# GRLV_DoubleRail_V0_1.net
KiCad netlist of a schematic drawn in Altium Designer
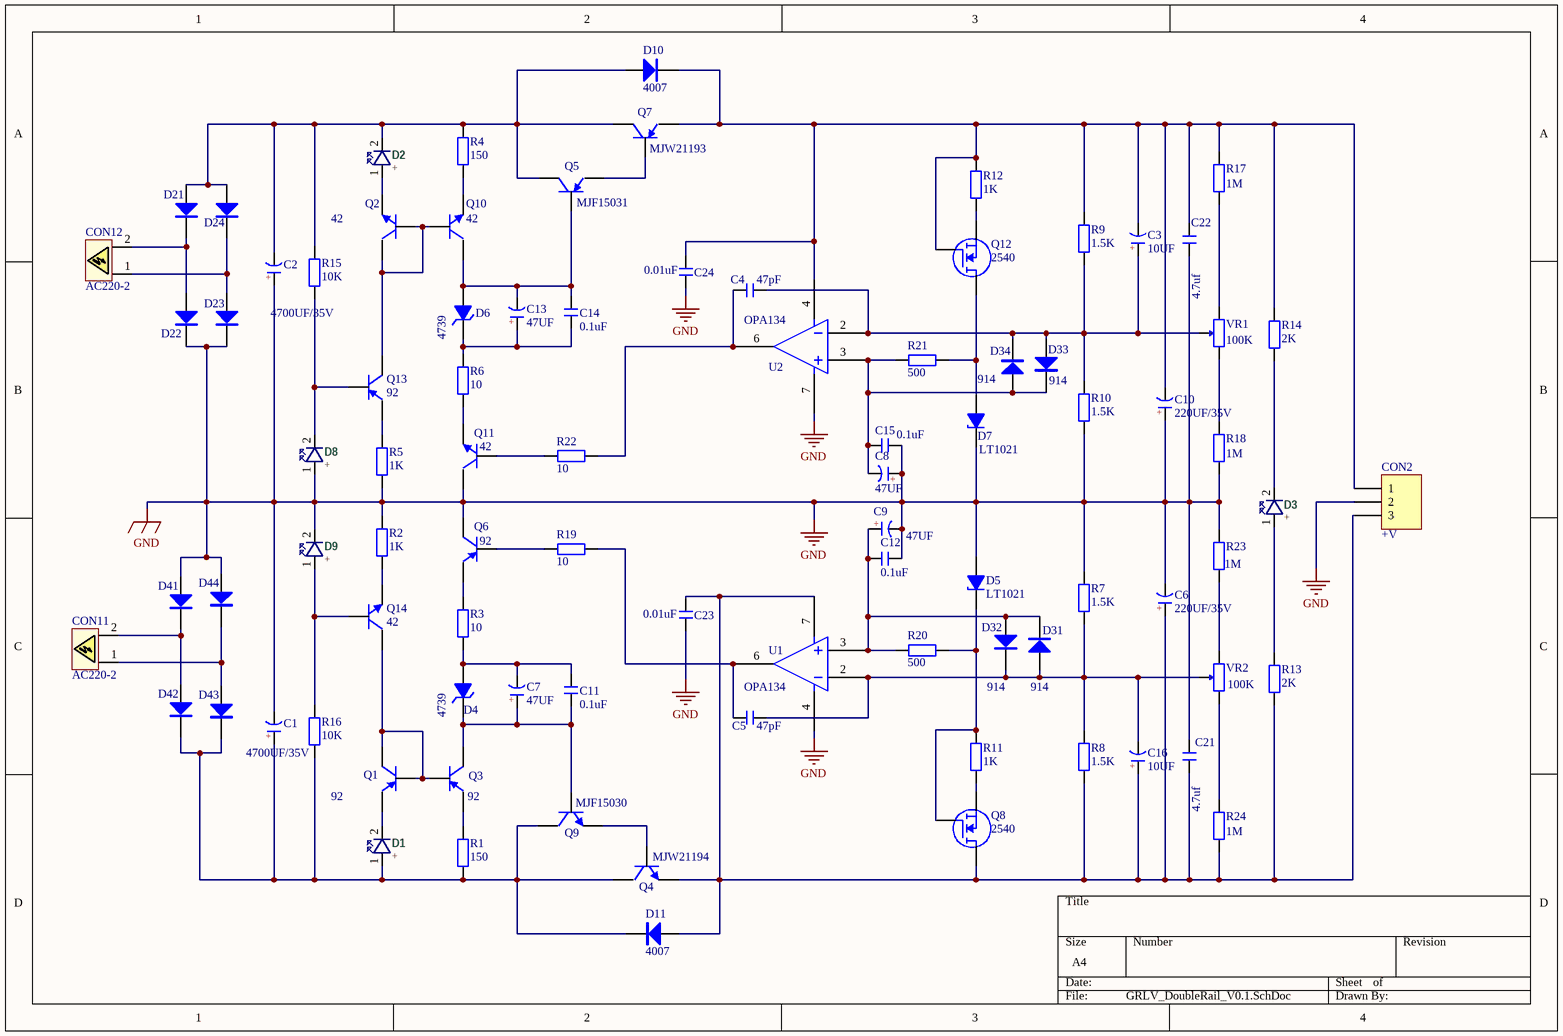
[diagram p0: GRLV_DoubleRail_V0.1.SchDoc]

(export (version "E")
  (design (tool "Eeschema 10.0.6"))
  (components
    (comp (ref "C1")
      (value "4700UF/35V")
      (footprint "CAP 11*35*60")
      (description "直插电解电容")
      (fields (field (name "版权归属") "源创客"))
      (libsource (lib "电阻-电容-电感") (part "C-CAP"))
    )
    (comp (ref "C2")
      (value "4700UF/35V")
      (footprint "CAP 11*35*60")
      (description "直插电解电容")
      (fields (field (name "版权归属") "源创客"))
      (libsource (lib "电阻-电容-电感") (part "C-CAP"))
    )
    (comp (ref "C3")
      (value "10UF")
      (footprint "CAP 2.5*6.3*7")
      (description "直插电解电容")
      (fields (field (name "版权归属") "源创客"))
      (libsource (lib "电阻-电容-电感") (part "C-CAP"))
    )
    (comp (ref "C4")
      (value "47pF")
      (footprint "CBB 6.3*6.3*5")
      (description "CBB电容")
      (fields (field (name "版权归属") "源创客"))
      (libsource (lib "电阻-电容-电感") (part "C-CBB"))
    )
    (comp (ref "C5")
      (value "47pF")
      (footprint "CBB 6.3*6.3*5")
      (description "CBB电容")
      (fields (field (name "版权归属") "源创客"))
      (libsource (lib "电阻-电容-电感") (part "C-CBB"))
    )
    (comp (ref "C6")
      (value "220UF/35V")
      (footprint "CAP 3.5*8*11.5")
      (description "直插电解电容")
      (fields (field (name "版权归属") "源创客"))
      (libsource (lib "电阻-电容-电感") (part "C-CAP"))
    )
    (comp (ref "C7")
      (value "47UF")
      (footprint "CAP 2.5*6.3*11.2")
      (description "直插电解电容")
      (fields (field (name "版权归属") "源创客"))
      (libsource (lib "电阻-电容-电感") (part "C-CAP"))
    )
    (comp (ref "C8")
      (value "47UF")
      (footprint "CAP 2.5*6.3*11.2")
      (description "直插电解电容")
      (fields (field (name "版权归属") "源创客"))
      (libsource (lib "") (part "C-CAP_1"))
    )
    (comp (ref "C9")
      (value "47UF")
      (footprint "CAP 2.5*6.3*11.2")
      (description "直插电解电容")
      (fields (field (name "版权归属") "源创客"))
      (libsource (lib "") (part "C-CAP_1"))
    )
    (comp (ref "C10")
      (value "220UF/35V")
      (footprint "CAP 3.5*8*11.5")
      (description "直插电解电容")
      (fields (field (name "版权归属") "源创客"))
      (libsource (lib "电阻-电容-电感") (part "C-CAP"))
    )
    (comp (ref "C11")
      (value "0.1uF")
      (footprint "CBB 6.3*6.3*5")
      (description "CBB电容")
      (fields (field (name "版权归属") "源创客"))
      (libsource (lib "电阻-电容-电感") (part "C-CBB"))
    )
    (comp (ref "C12")
      (value "0.1uF")
      (footprint "CBB 6.3*6.3*5")
      (description "CBB电容")
      (fields (field (name "版权归属") "源创客"))
      (libsource (lib "电阻-电容-电感") (part "C-CBB"))
    )
    (comp (ref "C13")
      (value "47UF")
      (footprint "CAP 2.5*6.3*11.2")
      (description "直插电解电容")
      (fields (field (name "版权归属") "源创客"))
      (libsource (lib "电阻-电容-电感") (part "C-CAP"))
    )
    (comp (ref "C14")
      (value "0.1uF")
      (footprint "CBB 6.3*6.3*5")
      (description "CBB电容")
      (fields (field (name "版权归属") "源创客"))
      (libsource (lib "电阻-电容-电感") (part "C-CBB"))
    )
    (comp (ref "C15")
      (value "0.1uF")
      (footprint "CBB 6.3*6.3*5")
      (description "CBB电容")
      (fields (field (name "版权归属") "源创客"))
      (libsource (lib "电阻-电容-电感") (part "C-CBB"))
    )
    (comp (ref "C16")
      (value "10UF")
      (footprint "CAP 2.5*6.3*7")
      (description "直插电解电容")
      (fields (field (name "版权归属") "源创客"))
      (libsource (lib "电阻-电容-电感") (part "C-CAP"))
    )
    (comp (ref "C21")
      (value "4.7uf")
      (footprint "CBB 7.2*7.2*13")
      (description "MKS薄膜电容")
      (libsource (lib "电阻-电容-电感") (part "C-MKS"))
    )
    (comp (ref "C22")
      (value "4.7uf")
      (footprint "CBB 7.2*7.2*13")
      (description "MKS薄膜电容")
      (libsource (lib "电阻-电容-电感") (part "C-MKS"))
    )
    (comp (ref "C23")
      (value "0.01uF")
      (footprint "CBB 6.3*6.3*5")
      (description "CBB电容")
      (fields (field (name "Comment") ".01") (field (name "版权归属") "源创客"))
      (libsource (lib "电阻-电容-电感") (part "C-CBB"))
    )
    (comp (ref "C24")
      (value "0.01uF")
      (footprint "CBB 6.3*6.3*5")
      (description "CBB电容")
      (fields (field (name "Comment") ".01") (field (name "版权归属") "源创客"))
      (libsource (lib "电阻-电容-电感") (part "C-CBB"))
    )
    (comp (ref "CON2")
      (value "+V")
      (footprint "HX5.08-3S")
      (libsource (lib "Connectors") (part "EDG5.08-3P"))
    )
    (comp (ref "CON11")
      (value "AC220-2")
      (footprint "HX5.08-2S")
      (libsource (lib "Connectors") (part "AC220-2"))
    )
    (comp (ref "CON12")
      (value "AC220-2")
      (footprint "HX5.08-2S")
      (libsource (lib "Connectors") (part "AC220-2"))
    )
    (comp (ref "D1")
      (value "+")
      (footprint "LED 3MM-R")
      (description "直插式LED")
      (libsource (lib "LED") (part "LED"))
    )
    (comp (ref "D2")
      (value "+")
      (footprint "LED 3MM-R")
      (description "直插式LED")
      (libsource (lib "LED") (part "LED"))
    )
    (comp (ref "D3")
      (value "+")
      (footprint "LED 3MM-R")
      (description "直插式LED")
      (libsource (lib "LED") (part "LED"))
    )
    (comp (ref "D4")
      (value "4739")
      (footprint "DO-41")
      (description "9.1V/1W稳压管")
      (libsource (lib "二极管-整流桥") (part "1N4739"))
    )
    (comp (ref "D5")
      (value "LT1021")
      (footprint "DIP8-300_MH")
      (description "10V Precision Reference 2 Pin Config")
      (libsource (lib "电压参考") (part "LT1021-10-2P"))
    )
    (comp (ref "D6")
      (value "4739")
      (footprint "DO-41")
      (description "9.1V/1W稳压管")
      (libsource (lib "二极管-整流桥") (part "1N4739"))
    )
    (comp (ref "D7")
      (value "LT1021")
      (footprint "DIP8-300_MH")
      (description "10V Precision Reference 2 Pin Config")
      (libsource (lib "电压参考") (part "LT1021-10-2P"))
    )
    (comp (ref "D8")
      (value "+")
      (footprint "LED 3MM-R")
      (description "直插式LED")
      (libsource (lib "LED") (part "LED"))
    )
    (comp (ref "D9")
      (value "+")
      (footprint "LED 3MM-R")
      (description "直插式LED")
      (libsource (lib "LED") (part "LED"))
    )
    (comp (ref "D10")
      (value "4007")
      (footprint "DO-41")
      (description "整流二极管")
      (fields (field (name "版权归属") "源创客"))
      (libsource (lib "二极管-整流桥") (part "1N4007"))
    )
    (comp (ref "D11")
      (value "4007")
      (footprint "DO-41")
      (description "整流二极管")
      (fields (field (name "版权归属") "源创客"))
      (libsource (lib "二极管-整流桥") (part "1N4007"))
    )
    (comp (ref "D21")
      (value "HFA08")
      (footprint "TO220AC")
      (description "Ultrafast Soft Recovery Diado 8A 600V")
      (libsource (lib "二极管-整流桥") (part "VS-HFA08TB60-M3"))
    )
    (comp (ref "D22")
      (value "HFA08")
      (footprint "TO220AC")
      (description "Ultrafast Soft Recovery Diado 8A 600V")
      (libsource (lib "二极管-整流桥") (part "VS-HFA08TB60-M3"))
    )
    (comp (ref "D23")
      (value "HFA08")
      (footprint "TO220AC")
      (description "Ultrafast Soft Recovery Diado 8A 600V")
      (libsource (lib "二极管-整流桥") (part "VS-HFA08TB60-M3"))
    )
    (comp (ref "D24")
      (value "HFA08")
      (footprint "TO220AC")
      (description "Ultrafast Soft Recovery Diado 8A 600V")
      (libsource (lib "二极管-整流桥") (part "VS-HFA08TB60-M3"))
    )
    (comp (ref "D31")
      (value "914")
      (footprint "DO-35")
      (description "高速开关管 1V/0.25W")
      (libsource (lib "二极管-整流桥") (part "1N914"))
    )
    (comp (ref "D32")
      (value "914")
      (footprint "DO-35")
      (description "高速开关管 1V/0.25W")
      (libsource (lib "二极管-整流桥") (part "1N914"))
    )
    (comp (ref "D33")
      (value "914")
      (footprint "DO-35")
      (description "高速开关管 1V/0.25W")
      (libsource (lib "二极管-整流桥") (part "1N914"))
    )
    (comp (ref "D34")
      (value "914")
      (footprint "DO-35")
      (description "高速开关管 1V/0.25W")
      (libsource (lib "二极管-整流桥") (part "1N914"))
    )
    (comp (ref "D41")
      (value "VS-HFA08TB60-M3")
      (footprint "TO220AC")
      (description "Ultrafast Soft Recovery Diado 8A 600V")
      (libsource (lib "二极管-整流桥") (part "VS-HFA08TB60-M3"))
    )
    (comp (ref "D42")
      (value "VS-HFA08TB60-M3")
      (footprint "TO220AC")
      (description "Ultrafast Soft Recovery Diado 8A 600V")
      (libsource (lib "二极管-整流桥") (part "VS-HFA08TB60-M3"))
    )
    (comp (ref "D43")
      (value "VS-HFA08TB60-M3")
      (footprint "TO220AC")
      (description "Ultrafast Soft Recovery Diado 8A 600V")
      (libsource (lib "二极管-整流桥") (part "VS-HFA08TB60-M3"))
    )
    (comp (ref "D44")
      (value "VS-HFA08TB60-M3")
      (footprint "TO220AC")
      (description "Ultrafast Soft Recovery Diado 8A 600V")
      (libsource (lib "二极管-整流桥") (part "VS-HFA08TB60-M3"))
    )
    (comp (ref "Q1")
      (value "92")
      (footprint "TO92A")
      (description "High Voltage PNP Transistor")
      (libsource (lib "三极管") (part "KSP92/93"))
    )
    (comp (ref "Q2")
      (value "42")
      (footprint "TO92A")
      (description "High Voltage NPN Transistor")
      (libsource (lib "三极管") (part "KSP42/43"))
    )
    (comp (ref "Q3")
      (value "92")
      (footprint "TO92A")
      (description "High Voltage PNP Transistor")
      (libsource (lib "三极管") (part "KSP92/93"))
    )
    (comp (ref "Q4")
      (value "MJW21194")
      (footprint "TO247V")
      (description "Power NPN Transistor")
      (libsource (lib "三极管") (part "MJW21194"))
    )
    (comp (ref "Q5")
      (value "MJF15031")
      (footprint "TO220V")
      (description "Power PNP Transistor")
      (libsource (lib "三极管") (part "MJF15031"))
    )
    (comp (ref "Q6")
      (value "92")
      (footprint "TO92A")
      (description "High Voltage PNP Transistor")
      (libsource (lib "三极管") (part "KSP92/93"))
    )
    (comp (ref "Q7")
      (value "MJW21193")
      (footprint "TO247V")
      (description "Power PNP Transistor")
      (libsource (lib "三极管") (part "MJW21193"))
    )
    (comp (ref "Q8")
      (value "2540")
      (footprint "TO92A")
      (description "N沟道耗尽型DMOS场效应管 400V/150ma")
      (libsource (lib "场效应管") (part "DN2540"))
    )
    (comp (ref "Q9")
      (value "MJF15030")
      (footprint "TO220V")
      (description "Power NPN Transistor")
      (libsource (lib "三极管") (part "MJF15030"))
    )
    (comp (ref "Q10")
      (value "42")
      (footprint "TO92A")
      (description "High Voltage NPN Transistor")
      (libsource (lib "三极管") (part "KSP42/43"))
    )
    (comp (ref "Q11")
      (value "42")
      (footprint "TO92A")
      (description "High Voltage NPN Transistor")
      (libsource (lib "三极管") (part "KSP42/43"))
    )
    (comp (ref "Q12")
      (value "2540")
      (footprint "TO92A")
      (description "N沟道耗尽型DMOS场效应管 400V/150ma")
      (libsource (lib "场效应管") (part "DN2540"))
    )
    (comp (ref "Q13")
      (value "92")
      (footprint "TO92A")
      (description "High Voltage PNP Transistor")
      (libsource (lib "三极管") (part "KSP92/93"))
    )
    (comp (ref "Q14")
      (value "42")
      (footprint "TO92A")
      (description "High Voltage NPN Transistor")
      (libsource (lib "三极管") (part "KSP42/43"))
    )
    (comp (ref "R1")
      (value "150")
      (footprint "RS 1/4W")
      (description "直插色环电阻")
      (fields (field (name "版权归属") "源创客"))
      (libsource (lib "电阻-电容-电感") (part "R-CRR"))
    )
    (comp (ref "R2")
      (value "1K")
      (footprint "RS 1/4W")
      (description "直插色环电阻")
      (fields (field (name "版权归属") "源创客"))
      (libsource (lib "电阻-电容-电感") (part "R-CRR"))
    )
    (comp (ref "R3")
      (value "10")
      (footprint "RS 1/4W")
      (description "直插色环电阻")
      (fields (field (name "版权归属") "源创客"))
      (libsource (lib "电阻-电容-电感") (part "R-CRR"))
    )
    (comp (ref "R4")
      (value "150")
      (footprint "RS 1/4W")
      (description "直插色环电阻")
      (fields (field (name "版权归属") "源创客"))
      (libsource (lib "电阻-电容-电感") (part "R-CRR"))
    )
    (comp (ref "R5")
      (value "1K")
      (footprint "RS 1/4W")
      (description "直插色环电阻")
      (fields (field (name "版权归属") "源创客"))
      (libsource (lib "电阻-电容-电感") (part "R-CRR"))
    )
    (comp (ref "R6")
      (value "10")
      (footprint "RS 1/4W")
      (description "直插色环电阻")
      (fields (field (name "版权归属") "源创客"))
      (libsource (lib "电阻-电容-电感") (part "R-CRR"))
    )
    (comp (ref "R7")
      (value "1.5K")
      (footprint "RS 1/4W")
      (description "直插色环电阻")
      (fields (field (name "版权归属") "源创客"))
      (libsource (lib "电阻-电容-电感") (part "R-CRR"))
    )
    (comp (ref "R8")
      (value "1.5K")
      (footprint "RS 1/4W")
      (description "直插色环电阻")
      (fields (field (name "版权归属") "源创客"))
      (libsource (lib "电阻-电容-电感") (part "R-CRR"))
    )
    (comp (ref "R9")
      (value "1.5K")
      (footprint "RS 1/4W")
      (description "直插色环电阻")
      (fields (field (name "版权归属") "源创客"))
      (libsource (lib "电阻-电容-电感") (part "R-CRR"))
    )
    (comp (ref "R10")
      (value "1.5K")
      (footprint "RS 1/4W")
      (description "直插色环电阻")
      (fields (field (name "版权归属") "源创客"))
      (libsource (lib "电阻-电容-电感") (part "R-CRR"))
    )
    (comp (ref "R11")
      (value "1K")
      (footprint "RS 1/4W")
      (description "直插色环电阻")
      (fields (field (name "版权归属") "源创客"))
      (libsource (lib "电阻-电容-电感") (part "R-CRR"))
    )
    (comp (ref "R12")
      (value "1K")
      (footprint "RS 1/4W")
      (description "直插色环电阻")
      (fields (field (name "版权归属") "源创客"))
      (libsource (lib "电阻-电容-电感") (part "R-CRR"))
    )
    (comp (ref "R13")
      (value "2K")
      (footprint "RS 1/4W")
      (description "直插色环电阻")
      (fields (field (name "版权归属") "源创客"))
      (libsource (lib "电阻-电容-电感") (part "R-CRR"))
    )
    (comp (ref "R14")
      (value "2K")
      (footprint "RS 1/4W")
      (description "直插色环电阻")
      (fields (field (name "版权归属") "源创客"))
      (libsource (lib "电阻-电容-电感") (part "R-CRR"))
    )
    (comp (ref "R15")
      (value "10K")
      (footprint "RS 1/4W")
      (description "直插色环电阻")
      (fields (field (name "版权归属") "源创客"))
      (libsource (lib "电阻-电容-电感") (part "R-CRR"))
    )
    (comp (ref "R16")
      (value "10K")
      (footprint "RS 1/4W")
      (description "直插色环电阻")
      (fields (field (name "版权归属") "源创客"))
      (libsource (lib "电阻-电容-电感") (part "R-CRR"))
    )
    (comp (ref "R17")
      (value "1M")
      (footprint "RS 1/4W")
      (description "直插色环电阻")
      (fields (field (name "版权归属") "源创客"))
      (libsource (lib "电阻-电容-电感") (part "R-CRR"))
    )
    (comp (ref "R18")
      (value "1M")
      (footprint "RS 1/4W")
      (description "直插色环电阻")
      (fields (field (name "版权归属") "源创客"))
      (libsource (lib "电阻-电容-电感") (part "R-CRR"))
    )
    (comp (ref "R19")
      (value "10")
      (footprint "RS 1/4W")
      (description "直插色环电阻")
      (fields (field (name "版权归属") "源创客"))
      (libsource (lib "电阻-电容-电感") (part "R-CRR"))
    )
    (comp (ref "R20")
      (value "500")
      (footprint "RS 1/4W")
      (description "直插色环电阻")
      (fields (field (name "版权归属") "源创客"))
      (libsource (lib "电阻-电容-电感") (part "R-CRR"))
    )
    (comp (ref "R21")
      (value "500")
      (footprint "RS 1/4W")
      (description "直插色环电阻")
      (fields (field (name "版权归属") "源创客"))
      (libsource (lib "电阻-电容-电感") (part "R-CRR"))
    )
    (comp (ref "R22")
      (value "10")
      (footprint "RS 1/4W")
      (description "直插色环电阻")
      (fields (field (name "版权归属") "源创客"))
      (libsource (lib "电阻-电容-电感") (part "R-CRR"))
    )
    (comp (ref "R23")
      (value "1M")
      (footprint "RS 1/4W")
      (description "直插色环电阻")
      (fields (field (name "版权归属") "源创客"))
      (libsource (lib "电阻-电容-电感") (part "R-CRR"))
    )
    (comp (ref "R24")
      (value "1M")
      (footprint "RS 1/4W")
      (description "直插色环电阻")
      (fields (field (name "版权归属") "源创客"))
      (libsource (lib "电阻-电容-电感") (part "R-CRR"))
    )
    (comp (ref "U1") (value "OPA134") (footprint "DIP8-300_MH") (libsource (lib "运放") (part "OPA134PA")))
    (comp (ref "U2") (value "OPA134") (footprint "DIP8-300_MH") (libsource (lib "运放") (part "OPA134PA")))
    (comp (ref "VR1")
      (value "100K")
      (footprint "RS 1/2W-VR")
      (description "直插可调电阻-顶调")
      (libsource (lib "电阻-电容-电感") (part "VR-W"))
    )
    (comp (ref "VR2")
      (value "100K")
      (footprint "RS 1/2W-VR")
      (description "直插可调电阻-顶调")
      (libsource (lib "电阻-电容-电感") (part "VR-W"))
    )
  )
  (nets
    (net (code "1") (name "GND") (class "Default")
      (node (ref "C1") (pin "2") (pinfunction "K_2") (pintype "passive"))
      (node (ref "C10") (pin "1") (pinfunction "A_1") (pintype "passive"))
      (node (ref "C12") (pin "2") (pinfunction "2_2") (pintype "passive"))
      (node (ref "C15") (pin "2") (pinfunction "2_2") (pintype "passive"))
      (node (ref "C2") (pin "1") (pinfunction "A_1") (pintype "passive"))
      (node (ref "C21") (pin "2") (pinfunction "2_2") (pintype "passive"))
      (node (ref "C22") (pin "1") (pinfunction "1_1") (pintype "passive"))
      (node (ref "C23") (pin "1") (pinfunction "1_1") (pintype "passive"))
      (node (ref "C24") (pin "1") (pinfunction "1_1") (pintype "passive"))
      (node (ref "C6") (pin "2") (pinfunction "K_2") (pintype "passive"))
      (node (ref "C8") (pin "1") (pinfunction "A_1") (pintype "passive"))
      (node (ref "C9") (pin "2") (pinfunction "K_2") (pintype "passive"))
      (node (ref "CON2") (pin "2") (pinfunction "2_2") (pintype "passive"))
      (node (ref "D22") (pin "1") (pinfunction "Cathode_1") (pintype "passive"))
      (node (ref "D23") (pin "1") (pinfunction "Cathode_1") (pintype "passive"))
      (node (ref "D41") (pin "2") (pinfunction "Anode_2") (pintype "passive"))
      (node (ref "D44") (pin "2") (pinfunction "Anode_2") (pintype "passive"))
      (node (ref "D5") (pin "4") (pinfunction "A_4") (pintype "passive"))
      (node (ref "D7") (pin "6") (pinfunction "K_6") (pintype "passive"))
      (node (ref "D8") (pin "1") (pinfunction "A_1") (pintype "passive"))
      (node (ref "D9") (pin "2") (pinfunction "K_2") (pintype "passive"))
      (node (ref "Q11") (pin "3") (pinfunction "C_3") (pintype "passive"))
      (node (ref "Q6") (pin "3") (pinfunction "C_3") (pintype "passive"))
      (node (ref "R10") (pin "1") (pinfunction "1_1") (pintype "passive"))
      (node (ref "R18") (pin "1") (pinfunction "1_1") (pintype "passive"))
      (node (ref "R2") (pin "2") (pinfunction "2_2") (pintype "passive"))
      (node (ref "R23") (pin "2") (pinfunction "2_2") (pintype "passive"))
      (node (ref "R5") (pin "1") (pinfunction "1_1") (pintype "passive"))
      (node (ref "R7") (pin "2") (pinfunction "2_2") (pintype "passive"))
      (node (ref "U1") (pin "4") (pinfunction "V-_4") (pintype "passive"))
      (node (ref "U2") (pin "7") (pinfunction "V+_7") (pintype "passive"))
    )
    (net (code "2") (name "Net-(C1-A)") (class "Default")
      (node (ref "C1") (pin "1") (pinfunction "A_1") (pintype "passive"))
      (node (ref "D1") (pin "1") (pinfunction "A_1") (pintype "passive"))
      (node (ref "D11") (pin "2") (pinfunction "K_2") (pintype "passive"))
      (node (ref "D42") (pin "1") (pinfunction "Cathode_1") (pintype "passive"))
      (node (ref "D43") (pin "1") (pinfunction "Cathode_1") (pintype "passive"))
      (node (ref "Q4") (pin "2") (pinfunction "C_2") (pintype "passive"))
      (node (ref "Q9") (pin "2") (pinfunction "C_2") (pintype "passive"))
      (node (ref "R1") (pin "1") (pinfunction "1_1") (pintype "passive"))
      (node (ref "R16") (pin "1") (pinfunction "1_1") (pintype "passive"))
    )
    (net (code "3") (name "Net-(C2-K)") (class "Default")
      (node (ref "C2") (pin "2") (pinfunction "K_2") (pintype "passive"))
      (node (ref "D10") (pin "1") (pinfunction "A_1") (pintype "passive"))
      (node (ref "D2") (pin "2") (pinfunction "K_2") (pintype "passive"))
      (node (ref "D21") (pin "2") (pinfunction "Anode_2") (pintype "passive"))
      (node (ref "D24") (pin "2") (pinfunction "Anode_2") (pintype "passive"))
      (node (ref "Q5") (pin "2") (pinfunction "C_2") (pintype "passive"))
      (node (ref "Q7") (pin "2") (pinfunction "C_2") (pintype "passive"))
      (node (ref "R15") (pin "2") (pinfunction "2_2") (pintype "passive"))
      (node (ref "R4") (pin "2") (pinfunction "2_2") (pintype "passive"))
    )
    (net (code "4") (name "Net-(C3-A)") (class "Default")
      (node (ref "C3") (pin "1") (pinfunction "A_1") (pintype "passive"))
      (node (ref "C4") (pin "2") (pinfunction "2_2") (pintype "passive"))
      (node (ref "D33") (pin "1") (pinfunction "A_1") (pintype "passive"))
      (node (ref "D34") (pin "2") (pinfunction "K_2") (pintype "passive"))
      (node (ref "R10") (pin "2") (pinfunction "2_2") (pintype "passive"))
      (node (ref "R9") (pin "1") (pinfunction "1_1") (pintype "passive"))
      (node (ref "U2") (pin "2") (pinfunction "-in_2") (pintype "passive"))
      (node (ref "VR1") (pin "3") (pinfunction "3_3") (pintype "passive"))
    )
    (net (code "5") (name "Net-(C7-A)") (class "Default")
      (node (ref "C11") (pin "1") (pinfunction "1_1") (pintype "passive"))
      (node (ref "C7") (pin "1") (pinfunction "A_1") (pintype "passive"))
      (node (ref "D4") (pin "2") (pinfunction "K_2") (pintype "passive"))
      (node (ref "Q3") (pin "3") (pinfunction "C_3") (pintype "passive"))
      (node (ref "Q9") (pin "1") (pinfunction "B_1") (pintype "passive"))
    )
    (net (code "6") (name "Net-(C7-K)") (class "Default")
      (node (ref "C11") (pin "2") (pinfunction "2_2") (pintype "passive"))
      (node (ref "C7") (pin "2") (pinfunction "K_2") (pintype "passive"))
      (node (ref "D4") (pin "1") (pinfunction "A_1") (pintype "passive"))
      (node (ref "R3") (pin "1") (pinfunction "1_1") (pintype "passive"))
    )
    (net (code "7") (name "Net-(C8-K)") (class "Default")
      (node (ref "C15") (pin "1") (pinfunction "1_1") (pintype "passive"))
      (node (ref "C8") (pin "2") (pinfunction "K_2") (pintype "passive"))
      (node (ref "D33") (pin "2") (pinfunction "K_2") (pintype "passive"))
      (node (ref "D34") (pin "1") (pinfunction "A_1") (pintype "passive"))
      (node (ref "R21") (pin "1") (pinfunction "1_1") (pintype "passive"))
      (node (ref "U2") (pin "3") (pinfunction "+in_3") (pintype "passive"))
    )
    (net (code "8") (name "Net-(C9-A)") (class "Default")
      (node (ref "C12") (pin "1") (pinfunction "1_1") (pintype "passive"))
      (node (ref "C9") (pin "1") (pinfunction "A_1") (pintype "passive"))
      (node (ref "D31") (pin "2") (pinfunction "K_2") (pintype "passive"))
      (node (ref "D32") (pin "1") (pinfunction "A_1") (pintype "passive"))
      (node (ref "R20") (pin "1") (pinfunction "1_1") (pintype "passive"))
      (node (ref "U1") (pin "3") (pinfunction "+in_3") (pintype "passive"))
    )
    (net (code "9") (name "Net-(C10-K)") (class "Default")
      (node (ref "C10") (pin "2") (pinfunction "K_2") (pintype "passive"))
      (node (ref "C22") (pin "2") (pinfunction "2_2") (pintype "passive"))
      (node (ref "C24") (pin "2") (pinfunction "2_2") (pintype "passive"))
      (node (ref "C3") (pin "2") (pinfunction "K_2") (pintype "passive"))
      (node (ref "CON2") (pin "1") (pinfunction "1_1") (pintype "passive"))
      (node (ref "D10") (pin "2") (pinfunction "K_2") (pintype "passive"))
      (node (ref "Q12") (pin "2") (pinfunction "G_2") (pintype "passive"))
      (node (ref "Q7") (pin "3") (pinfunction "E_3") (pintype "passive"))
      (node (ref "R12") (pin "2") (pinfunction "2_2") (pintype "passive"))
      (node (ref "R14") (pin "2") (pinfunction "2_2") (pintype "passive"))
      (node (ref "R17") (pin "2") (pinfunction "2_2") (pintype "passive"))
      (node (ref "R9") (pin "2") (pinfunction "2_2") (pintype "passive"))
      (node (ref "U2") (pin "4") (pinfunction "V-_4") (pintype "passive"))
    )
    (net (code "10") (name "Net-(C13-A)") (class "Default")
      (node (ref "C13") (pin "1") (pinfunction "A_1") (pintype "passive"))
      (node (ref "C14") (pin "1") (pinfunction "1_1") (pintype "passive"))
      (node (ref "D6") (pin "2") (pinfunction "K_2") (pintype "passive"))
      (node (ref "R6") (pin "2") (pinfunction "2_2") (pintype "passive"))
    )
    (net (code "11") (name "Net-(C13-K)") (class "Default")
      (node (ref "C13") (pin "2") (pinfunction "K_2") (pintype "passive"))
      (node (ref "C14") (pin "2") (pinfunction "2_2") (pintype "passive"))
      (node (ref "D6") (pin "1") (pinfunction "A_1") (pintype "passive"))
      (node (ref "Q10") (pin "3") (pinfunction "C_3") (pintype "passive"))
      (node (ref "Q5") (pin "1") (pinfunction "B_1") (pintype "passive"))
    )
    (net (code "12") (name "Net-(C16-A)") (class "Default")
      (node (ref "C16") (pin "1") (pinfunction "A_1") (pintype "passive"))
      (node (ref "C21") (pin "1") (pinfunction "1_1") (pintype "passive"))
      (node (ref "C23") (pin "2") (pinfunction "2_2") (pintype "passive"))
      (node (ref "C6") (pin "1") (pinfunction "A_1") (pintype "passive"))
      (node (ref "CON2") (pin "3") (pinfunction "3_3") (pintype "passive"))
      (node (ref "D11") (pin "1") (pinfunction "A_1") (pintype "passive"))
      (node (ref "Q4") (pin "3") (pinfunction "E_3") (pintype "passive"))
      (node (ref "Q8") (pin "3") (pinfunction "D_3") (pintype "passive"))
      (node (ref "R13") (pin "2") (pinfunction "2_2") (pintype "passive"))
      (node (ref "R24") (pin "1") (pinfunction "1_1") (pintype "passive"))
      (node (ref "R8") (pin "1") (pinfunction "1_1") (pintype "passive"))
      (node (ref "U1") (pin "7") (pinfunction "V+_7") (pintype "passive"))
    )
    (net (code "13") (name "Net-(C16-K)") (class "Default")
      (node (ref "C16") (pin "2") (pinfunction "K_2") (pintype "passive"))
      (node (ref "C5") (pin "2") (pinfunction "2_2") (pintype "passive"))
      (node (ref "D31") (pin "1") (pinfunction "A_1") (pintype "passive"))
      (node (ref "D32") (pin "2") (pinfunction "K_2") (pintype "passive"))
      (node (ref "R7") (pin "1") (pinfunction "1_1") (pintype "passive"))
      (node (ref "R8") (pin "2") (pinfunction "2_2") (pintype "passive"))
      (node (ref "U1") (pin "2") (pinfunction "-in_2") (pintype "passive"))
      (node (ref "VR2") (pin "3") (pinfunction "3_3") (pintype "passive"))
    )
    (net (code "14") (name "Net-(CON11-G)") (class "Default")
      (node (ref "CON11") (pin "2") (pinfunction "G_2") (pintype "passive"))
      (node (ref "D41") (pin "1") (pinfunction "Cathode_1") (pintype "passive"))
      (node (ref "D42") (pin "2") (pinfunction "Anode_2") (pintype "passive"))
    )
    (net (code "15") (name "Net-(CON11-L)") (class "Default")
      (node (ref "CON11") (pin "1") (pinfunction "L_1") (pintype "passive"))
      (node (ref "D43") (pin "2") (pinfunction "Anode_2") (pintype "passive"))
      (node (ref "D44") (pin "1") (pinfunction "Cathode_1") (pintype "passive"))
    )
    (net (code "16") (name "Net-(CON12-G)") (class "Default")
      (node (ref "CON12") (pin "2") (pinfunction "G_2") (pintype "passive"))
      (node (ref "D21") (pin "1") (pinfunction "Cathode_1") (pintype "passive"))
      (node (ref "D22") (pin "2") (pinfunction "Anode_2") (pintype "passive"))
    )
    (net (code "17") (name "Net-(CON12-L)") (class "Default")
      (node (ref "CON12") (pin "1") (pinfunction "L_1") (pintype "passive"))
      (node (ref "D23") (pin "2") (pinfunction "Anode_2") (pintype "passive"))
      (node (ref "D24") (pin "1") (pinfunction "Cathode_1") (pintype "passive"))
    )
    (net (code "18") (name "Net-(D1-K)") (class "Default")
      (node (ref "D1") (pin "2") (pinfunction "K_2") (pintype "passive"))
      (node (ref "Q1") (pin "1") (pinfunction "E_1") (pintype "passive"))
    )
    (net (code "19") (name "Net-(D2-A)") (class "Default")
      (node (ref "D2") (pin "1") (pinfunction "A_1") (pintype "passive"))
      (node (ref "Q2") (pin "1") (pinfunction "E_1") (pintype "passive"))
    )
    (net (code "20") (name "Net-(D3-A)") (class "Default")
      (node (ref "D3") (pin "1") (pinfunction "A_1") (pintype "passive"))
      (node (ref "R13") (pin "1") (pinfunction "1_1") (pintype "passive"))
    )
    (net (code "21") (name "Net-(D3-K)") (class "Default")
      (node (ref "D3") (pin "2") (pinfunction "K_2") (pintype "passive"))
      (node (ref "R14") (pin "1") (pinfunction "1_1") (pintype "passive"))
    )
    (net (code "22") (name "Net-(D5-K)") (class "Default")
      (node (ref "D5") (pin "6") (pinfunction "K_6") (pintype "passive"))
      (node (ref "Q8") (pin "2") (pinfunction "G_2") (pintype "passive"))
      (node (ref "R11") (pin "2") (pinfunction "2_2") (pintype "passive"))
      (node (ref "R20") (pin "2") (pinfunction "2_2") (pintype "passive"))
    )
    (net (code "23") (name "Net-(D7-A)") (class "Default")
      (node (ref "D7") (pin "4") (pinfunction "A_4") (pintype "passive"))
      (node (ref "Q12") (pin "3") (pinfunction "D_3") (pintype "passive"))
      (node (ref "R21") (pin "2") (pinfunction "2_2") (pintype "passive"))
    )
    (net (code "24") (name "Net-(D8-K)") (class "Default")
      (node (ref "D8") (pin "2") (pinfunction "K_2") (pintype "passive"))
      (node (ref "Q13") (pin "2") (pinfunction "B_2") (pintype "passive"))
      (node (ref "R15") (pin "1") (pinfunction "1_1") (pintype "passive"))
    )
    (net (code "25") (name "Net-(D9-A)") (class "Default")
      (node (ref "D9") (pin "1") (pinfunction "A_1") (pintype "passive"))
      (node (ref "Q14") (pin "2") (pinfunction "B_2") (pintype "passive"))
      (node (ref "R16") (pin "2") (pinfunction "2_2") (pintype "passive"))
    )
    (net (code "26") (name "Net-(Q1-B)") (class "Default")
      (node (ref "Q1") (pin "2") (pinfunction "B_2") (pintype "passive"))
      (node (ref "Q1") (pin "3") (pinfunction "C_3") (pintype "passive"))
      (node (ref "Q14") (pin "3") (pinfunction "C_3") (pintype "passive"))
      (node (ref "Q3") (pin "2") (pinfunction "B_2") (pintype "passive"))
    )
    (net (code "27") (name "Net-(Q3-E)") (class "Default")
      (node (ref "Q3") (pin "1") (pinfunction "E_1") (pintype "passive"))
      (node (ref "R1") (pin "2") (pinfunction "2_2") (pintype "passive"))
    )
    (net (code "28") (name "Net-(Q4-B)") (class "Default")
      (node (ref "Q4") (pin "1") (pinfunction "B_1") (pintype "passive"))
      (node (ref "Q9") (pin "3") (pinfunction "E_3") (pintype "passive"))
    )
    (net (code "29") (name "Net-(Q5-E)") (class "Default")
      (node (ref "Q5") (pin "3") (pinfunction "E_3") (pintype "passive"))
      (node (ref "Q7") (pin "1") (pinfunction "B_1") (pintype "passive"))
    )
    (net (code "30") (name "Net-(Q6-B)") (class "Default")
      (node (ref "Q6") (pin "2") (pinfunction "B_2") (pintype "passive"))
      (node (ref "R19") (pin "1") (pinfunction "1_1") (pintype "passive"))
    )
    (net (code "31") (name "Net-(Q6-E)") (class "Default")
      (node (ref "Q6") (pin "1") (pinfunction "E_1") (pintype "passive"))
      (node (ref "R3") (pin "2") (pinfunction "2_2") (pintype "passive"))
    )
    (net (code "32") (name "Net-(Q8-S)") (class "Default")
      (node (ref "Q8") (pin "1") (pinfunction "S_1") (pintype "passive"))
      (node (ref "R11") (pin "1") (pinfunction "1_1") (pintype "passive"))
    )
    (net (code "33") (name "Net-(Q10-B)") (class "Default")
      (node (ref "Q10") (pin "2") (pinfunction "B_2") (pintype "passive"))
      (node (ref "Q13") (pin "3") (pinfunction "C_3") (pintype "passive"))
      (node (ref "Q2") (pin "2") (pinfunction "B_2") (pintype "passive"))
      (node (ref "Q2") (pin "3") (pinfunction "C_3") (pintype "passive"))
    )
    (net (code "34") (name "Net-(Q10-E)") (class "Default")
      (node (ref "Q10") (pin "1") (pinfunction "E_1") (pintype "passive"))
      (node (ref "R4") (pin "1") (pinfunction "1_1") (pintype "passive"))
    )
    (net (code "35") (name "Net-(Q11-B)") (class "Default")
      (node (ref "Q11") (pin "2") (pinfunction "B_2") (pintype "passive"))
      (node (ref "R22") (pin "1") (pinfunction "1_1") (pintype "passive"))
    )
    (net (code "36") (name "Net-(Q11-E)") (class "Default")
      (node (ref "Q11") (pin "1") (pinfunction "E_1") (pintype "passive"))
      (node (ref "R6") (pin "1") (pinfunction "1_1") (pintype "passive"))
    )
    (net (code "37") (name "Net-(Q12-S)") (class "Default")
      (node (ref "Q12") (pin "1") (pinfunction "S_1") (pintype "passive"))
      (node (ref "R12") (pin "1") (pinfunction "1_1") (pintype "passive"))
    )
    (net (code "38") (name "Net-(Q13-E)") (class "Default")
      (node (ref "Q13") (pin "1") (pinfunction "E_1") (pintype "passive"))
      (node (ref "R5") (pin "2") (pinfunction "2_2") (pintype "passive"))
    )
    (net (code "39") (name "Net-(Q14-E)") (class "Default")
      (node (ref "Q14") (pin "1") (pinfunction "E_1") (pintype "passive"))
      (node (ref "R2") (pin "1") (pinfunction "1_1") (pintype "passive"))
    )
    (net (code "40") (name "Net-(R17-Pad1)") (class "Default")
      (node (ref "R17") (pin "1") (pinfunction "1_1") (pintype "passive"))
      (node (ref "VR1") (pin "2") (pinfunction "2_2") (pintype "passive"))
    )
    (net (code "41") (name "Net-(R18-Pad2)") (class "Default")
      (node (ref "R18") (pin "2") (pinfunction "2_2") (pintype "passive"))
      (node (ref "VR1") (pin "1") (pinfunction "1_1") (pintype "passive"))
    )
    (net (code "42") (name "Net-(R23-Pad1)") (class "Default")
      (node (ref "R23") (pin "1") (pinfunction "1_1") (pintype "passive"))
      (node (ref "VR2") (pin "2") (pinfunction "2_2") (pintype "passive"))
    )
    (net (code "43") (name "Net-(R24-Pad2)") (class "Default")
      (node (ref "R24") (pin "2") (pinfunction "2_2") (pintype "passive"))
      (node (ref "VR2") (pin "1") (pinfunction "1_1") (pintype "passive"))
    )
    (net (code "44") (name "Net-(U1-out)") (class "Default")
      (node (ref "C5") (pin "1") (pinfunction "1_1") (pintype "passive"))
      (node (ref "R19") (pin "2") (pinfunction "2_2") (pintype "passive"))
      (node (ref "U1") (pin "6") (pinfunction "out_6") (pintype "passive"))
    )
    (net (code "45") (name "Net-(U2-out)") (class "Default")
      (node (ref "C4") (pin "1") (pinfunction "1_1") (pintype "passive"))
      (node (ref "R22") (pin "2") (pinfunction "2_2") (pintype "passive"))
      (node (ref "U2") (pin "6") (pinfunction "out_6") (pintype "passive"))
    )
  )
)
